# Module_I2C_TOF.net
KiCad netlist of a schematic drawn in EAGLE
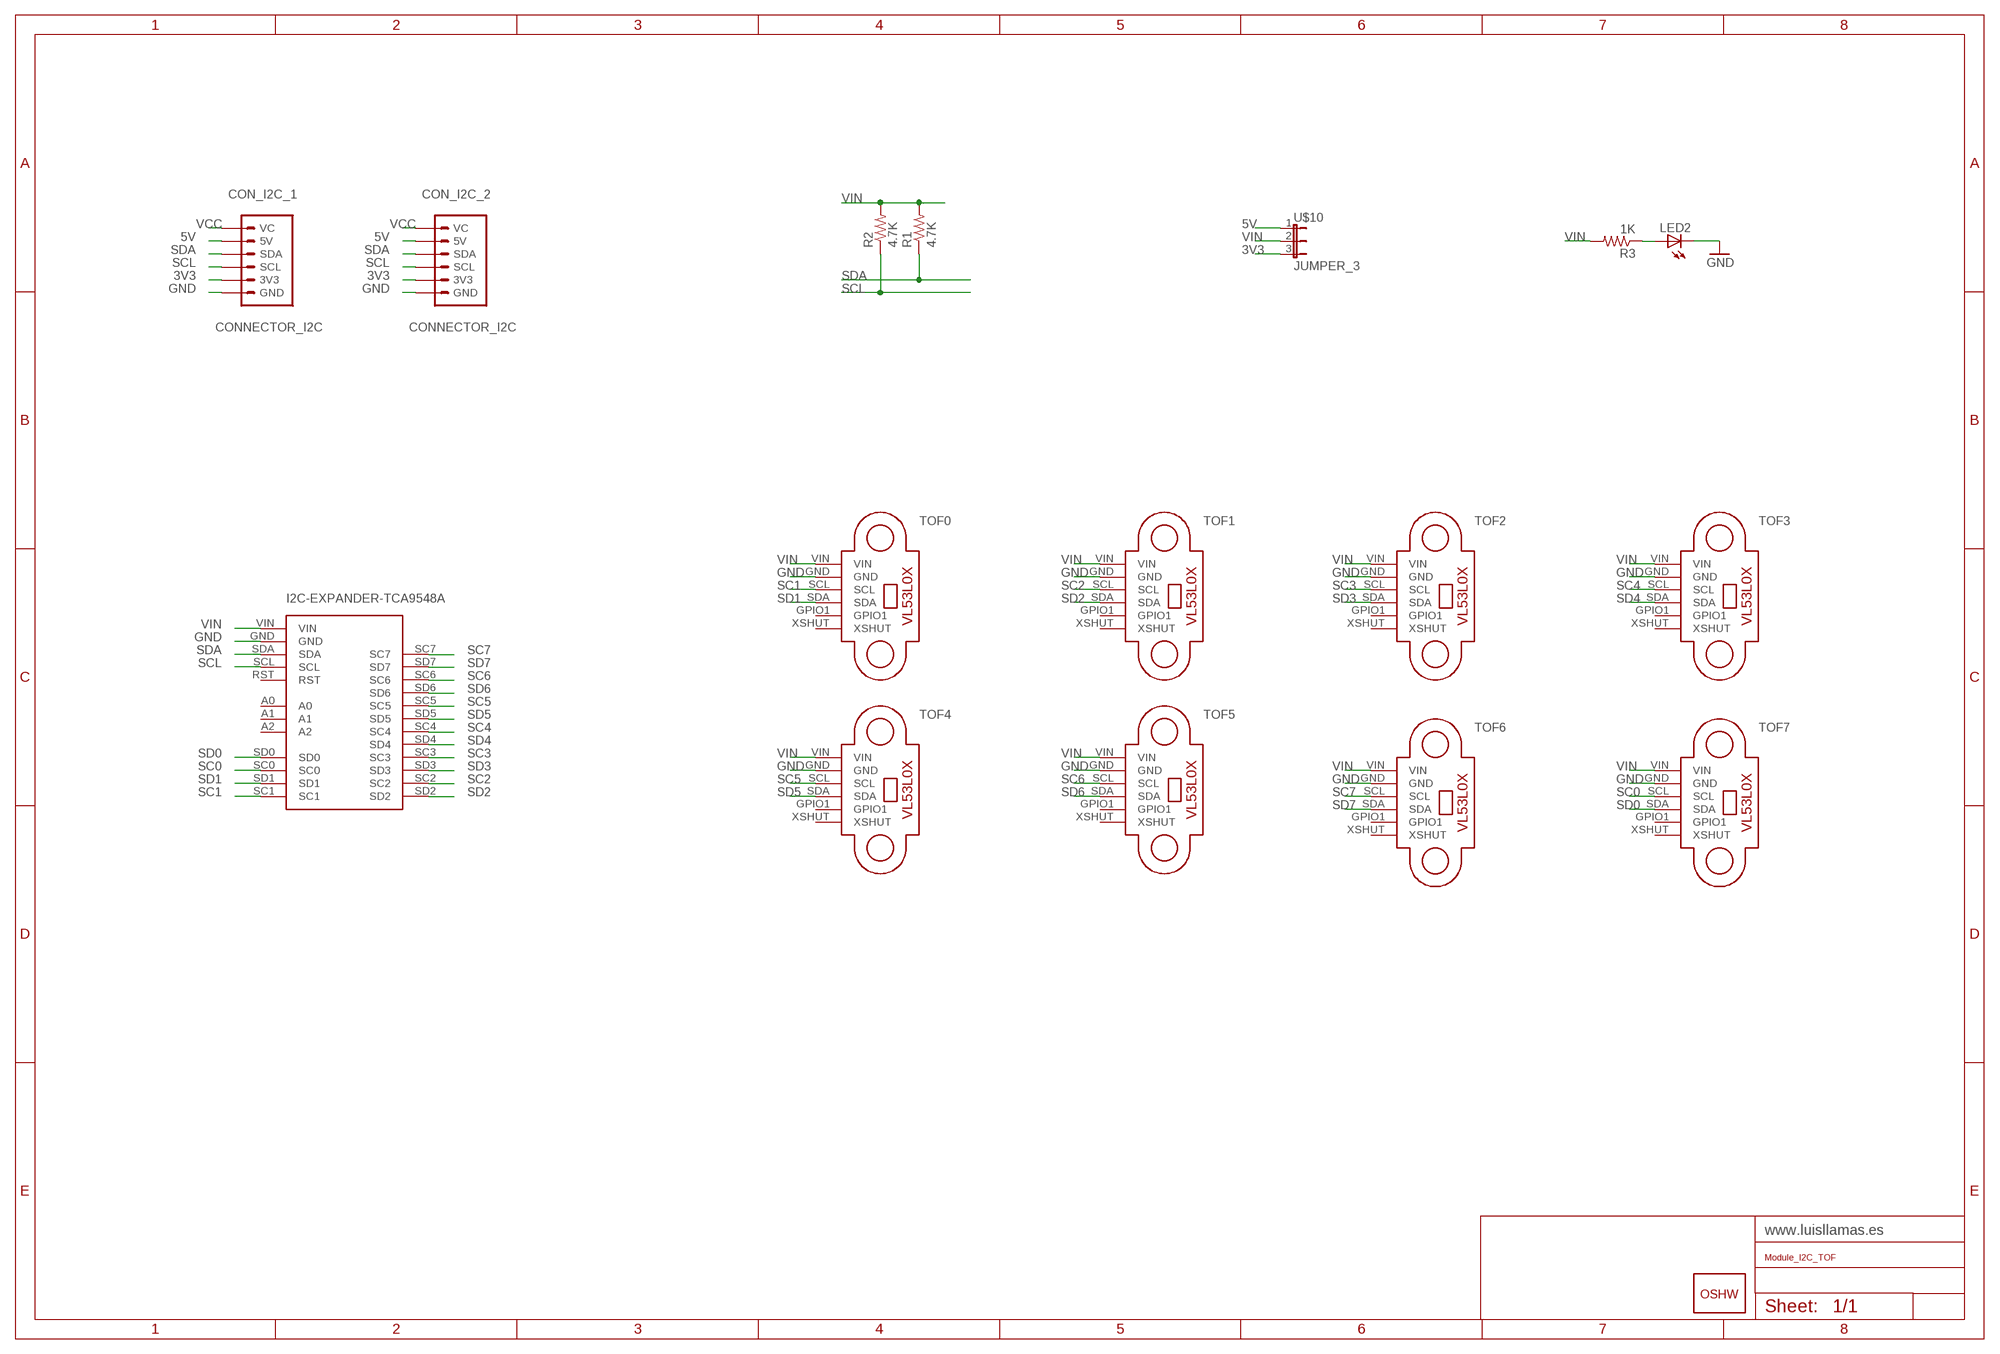
[diagram p0: schematic, sheet 1]

(export (version "E")
  (design (tool "Eeschema 10.0.6"))
  (components
    (comp (ref "CON_I2C_1")
      (value "CONNECTOR_I2C")
      (footprint "eagle-import:CONNECTOR_I2C")
      (libsource (lib "eagle-import") (part "CONNECTOR_I2C"))
    )
    (comp (ref "CON_I2C_2")
      (value "CONNECTOR_I2C")
      (footprint "eagle-import:CONNECTOR_I2C")
      (libsource (lib "eagle-import") (part "CONNECTOR_I2C"))
    )
    (comp (ref "GOLD_ORB_SM1")
      (value "OSHWLOGO_GOLD_ORB_MED")
      (footprint "eagle-import:OSHW1")
      (libsource (lib "eagle-import") (part "OSHWLOGO_GOLD_ORB_MED"))
    )
    (comp (ref "LED2")
      (value "LEDCHIP-LED0805")
      (footprint "eagle-import:CHIP-LED0805")
      (libsource (lib "eagle-import") (part "LEDCHIP-LED0805"))
    )
    (comp (ref "R1")
      (value "4.7K")
      (footprint "eagle-import:R0805")
      (libsource (lib "eagle-import") (part "R-US_R0805"))
    )
    (comp (ref "R2")
      (value "4.7K")
      (footprint "eagle-import:R0805")
      (libsource (lib "eagle-import") (part "R-US_R0805"))
    )
    (comp (ref "R3")
      (value "1K")
      (footprint "eagle-import:R0805")
      (libsource (lib "eagle-import") (part "R-US_R0805"))
    )
    (comp (ref "TOF0")
      (value "RANGING-SENSOR-VL53L0X")
      (footprint "eagle-import:RANGING-SENSOR-VL53L0X")
      (libsource (lib "eagle-import") (part "RANGING-SENSOR-VL53L0X"))
    )
    (comp (ref "TOF1")
      (value "RANGING-SENSOR-VL53L0X")
      (footprint "eagle-import:RANGING-SENSOR-VL53L0X")
      (libsource (lib "eagle-import") (part "RANGING-SENSOR-VL53L0X"))
    )
    (comp (ref "TOF2")
      (value "RANGING-SENSOR-VL53L0X")
      (footprint "eagle-import:RANGING-SENSOR-VL53L0X")
      (libsource (lib "eagle-import") (part "RANGING-SENSOR-VL53L0X"))
    )
    (comp (ref "TOF3")
      (value "RANGING-SENSOR-VL53L0X")
      (footprint "eagle-import:RANGING-SENSOR-VL53L0X")
      (libsource (lib "eagle-import") (part "RANGING-SENSOR-VL53L0X"))
    )
    (comp (ref "TOF4")
      (value "RANGING-SENSOR-VL53L0X")
      (footprint "eagle-import:RANGING-SENSOR-VL53L0X")
      (libsource (lib "eagle-import") (part "RANGING-SENSOR-VL53L0X"))
    )
    (comp (ref "TOF5")
      (value "RANGING-SENSOR-VL53L0X")
      (footprint "eagle-import:RANGING-SENSOR-VL53L0X")
      (libsource (lib "eagle-import") (part "RANGING-SENSOR-VL53L0X"))
    )
    (comp (ref "TOF6")
      (value "RANGING-SENSOR-VL53L0X")
      (footprint "eagle-import:RANGING-SENSOR-VL53L0X")
      (libsource (lib "eagle-import") (part "RANGING-SENSOR-VL53L0X"))
    )
    (comp (ref "TOF7")
      (value "RANGING-SENSOR-VL53L0X")
      (footprint "eagle-import:RANGING-SENSOR-VL53L0X")
      (libsource (lib "eagle-import") (part "RANGING-SENSOR-VL53L0X"))
    )
    (comp (ref "U$9")
      (value "I2C-EXPANDER-TCA9548A")
      (footprint "eagle-import:I2C-EXPANDER-TCA9548A")
      (libsource (lib "eagle-import") (part "I2C-EXPANDER-TCA9548A"))
    )
    (comp (ref "U$10")
      (value "JUMPER_3")
      (footprint "eagle-import:JUMPER_3")
      (libsource (lib "eagle-import") (part "JUMPER_3"))
    )
  )
  (nets
    (net (code "1") (name "/3V3") (class "Default")
      (node (ref "CON_I2C_1") (pin "3V3") (pinfunction "3V3_3V3") (pintype "passive"))
      (node (ref "CON_I2C_2") (pin "3V3") (pinfunction "3V3_3V3") (pintype "passive"))
      (node (ref "U$10") (pin "3") (pinfunction "3_3") (pintype "passive"))
    )
    (net (code "2") (name "/5V") (class "Default")
      (node (ref "CON_I2C_1") (pin "5V") (pinfunction "5V_5V") (pintype "passive"))
      (node (ref "CON_I2C_2") (pin "5V") (pinfunction "5V_5V") (pintype "passive"))
      (node (ref "U$10") (pin "1") (pinfunction "1_1") (pintype "passive"))
    )
    (net (code "3") (name "/SC0") (class "Default")
      (node (ref "TOF7") (pin "SCL") (pinfunction "SCL_SCL") (pintype "bidirectional"))
      (node (ref "U$9") (pin "SC0") (pinfunction "SC0_SC0") (pintype "input"))
    )
    (net (code "4") (name "/SC1") (class "Default")
      (node (ref "TOF0") (pin "SCL") (pinfunction "SCL_SCL") (pintype "bidirectional"))
      (node (ref "U$9") (pin "SC1") (pinfunction "SC1_SC1") (pintype "input"))
    )
    (net (code "5") (name "/SC2") (class "Default")
      (node (ref "TOF1") (pin "SCL") (pinfunction "SCL_SCL") (pintype "bidirectional"))
      (node (ref "U$9") (pin "SC2") (pinfunction "SC2_SC2") (pintype "bidirectional"))
    )
    (net (code "6") (name "/SC3") (class "Default")
      (node (ref "TOF2") (pin "SCL") (pinfunction "SCL_SCL") (pintype "bidirectional"))
      (node (ref "U$9") (pin "SC3") (pinfunction "SC3_SC3") (pintype "bidirectional"))
    )
    (net (code "7") (name "/SC4") (class "Default")
      (node (ref "TOF3") (pin "SCL") (pinfunction "SCL_SCL") (pintype "bidirectional"))
      (node (ref "U$9") (pin "SC4") (pinfunction "SC4_SC4") (pintype "input"))
    )
    (net (code "8") (name "/SC5") (class "Default")
      (node (ref "TOF4") (pin "SCL") (pinfunction "SCL_SCL") (pintype "bidirectional"))
      (node (ref "U$9") (pin "SC5") (pinfunction "SC5_SC5") (pintype "input"))
    )
    (net (code "9") (name "/SC6") (class "Default")
      (node (ref "TOF5") (pin "SCL") (pinfunction "SCL_SCL") (pintype "bidirectional"))
      (node (ref "U$9") (pin "SC6") (pinfunction "SC6_SC6") (pintype "input"))
    )
    (net (code "10") (name "/SC7") (class "Default")
      (node (ref "TOF6") (pin "SCL") (pinfunction "SCL_SCL") (pintype "bidirectional"))
      (node (ref "U$9") (pin "SC7") (pinfunction "SC7_SC7") (pintype "input"))
    )
    (net (code "11") (name "/SCL") (class "Default")
      (node (ref "CON_I2C_1") (pin "SCL") (pinfunction "SCL_SCL") (pintype "passive"))
      (node (ref "CON_I2C_2") (pin "SCL") (pinfunction "SCL_SCL") (pintype "passive"))
      (node (ref "R2") (pin "1") (pinfunction "1_1") (pintype "passive"))
      (node (ref "U$9") (pin "SCL") (pinfunction "SCL_SCL") (pintype "bidirectional"))
    )
    (net (code "12") (name "/SD0") (class "Default")
      (node (ref "TOF7") (pin "SDA") (pinfunction "SDA_SDA") (pintype "bidirectional"))
      (node (ref "U$9") (pin "SD0") (pinfunction "SD0_SD0") (pintype "input"))
    )
    (net (code "13") (name "/SD1") (class "Default")
      (node (ref "TOF0") (pin "SDA") (pinfunction "SDA_SDA") (pintype "bidirectional"))
      (node (ref "U$9") (pin "SD1") (pinfunction "SD1_SD1") (pintype "input"))
    )
    (net (code "14") (name "/SD2") (class "Default")
      (node (ref "TOF1") (pin "SDA") (pinfunction "SDA_SDA") (pintype "bidirectional"))
      (node (ref "U$9") (pin "SD2") (pinfunction "SD2_SD2") (pintype "bidirectional"))
    )
    (net (code "15") (name "/SD3") (class "Default")
      (node (ref "TOF2") (pin "SDA") (pinfunction "SDA_SDA") (pintype "bidirectional"))
      (node (ref "U$9") (pin "SD3") (pinfunction "SD3_SD3") (pintype "bidirectional"))
    )
    (net (code "16") (name "/SD4") (class "Default")
      (node (ref "TOF3") (pin "SDA") (pinfunction "SDA_SDA") (pintype "bidirectional"))
      (node (ref "U$9") (pin "SD4") (pinfunction "SD4_SD4") (pintype "input"))
    )
    (net (code "17") (name "/SD5") (class "Default")
      (node (ref "TOF4") (pin "SDA") (pinfunction "SDA_SDA") (pintype "bidirectional"))
      (node (ref "U$9") (pin "SD5") (pinfunction "SD5_SD5") (pintype "input"))
    )
    (net (code "18") (name "/SD6") (class "Default")
      (node (ref "TOF5") (pin "SDA") (pinfunction "SDA_SDA") (pintype "bidirectional"))
      (node (ref "U$9") (pin "SD6") (pinfunction "SD6_SD6") (pintype "input"))
    )
    (net (code "19") (name "/SD7") (class "Default")
      (node (ref "TOF6") (pin "SDA") (pinfunction "SDA_SDA") (pintype "bidirectional"))
      (node (ref "U$9") (pin "SD7") (pinfunction "SD7_SD7") (pintype "input"))
    )
    (net (code "20") (name "/SDA") (class "Default")
      (node (ref "CON_I2C_1") (pin "SDA") (pinfunction "SDA_SDA") (pintype "passive"))
      (node (ref "CON_I2C_2") (pin "SDA") (pinfunction "SDA_SDA") (pintype "passive"))
      (node (ref "R1") (pin "1") (pinfunction "1_1") (pintype "passive"))
      (node (ref "U$9") (pin "SDA") (pinfunction "SDA_SDA") (pintype "bidirectional"))
    )
    (net (code "21") (name "/VCC") (class "Default")
      (node (ref "CON_I2C_1") (pin "VC") (pinfunction "VC_VC") (pintype "passive"))
      (node (ref "CON_I2C_2") (pin "VC") (pinfunction "VC_VC") (pintype "passive"))
    )
    (net (code "22") (name "/VIN") (class "Default")
      (node (ref "R1") (pin "2") (pinfunction "2_2") (pintype "passive"))
      (node (ref "R2") (pin "2") (pinfunction "2_2") (pintype "passive"))
      (node (ref "R3") (pin "2") (pinfunction "2_2") (pintype "passive"))
      (node (ref "TOF0") (pin "VIN") (pinfunction "VIN_VIN") (pintype "power_in"))
      (node (ref "TOF1") (pin "VIN") (pinfunction "VIN_VIN") (pintype "power_in"))
      (node (ref "TOF2") (pin "VIN") (pinfunction "VIN_VIN") (pintype "power_in"))
      (node (ref "TOF3") (pin "VIN") (pinfunction "VIN_VIN") (pintype "power_in"))
      (node (ref "TOF4") (pin "VIN") (pinfunction "VIN_VIN") (pintype "power_in"))
      (node (ref "TOF5") (pin "VIN") (pinfunction "VIN_VIN") (pintype "power_in"))
      (node (ref "TOF6") (pin "VIN") (pinfunction "VIN_VIN") (pintype "power_in"))
      (node (ref "TOF7") (pin "VIN") (pinfunction "VIN_VIN") (pintype "power_in"))
      (node (ref "U$10") (pin "2") (pinfunction "2_2") (pintype "passive"))
      (node (ref "U$9") (pin "VIN") (pinfunction "VIN_VIN") (pintype "power_in"))
    )
    (net (code "23") (name "GND") (class "Default")
      (node (ref "CON_I2C_1") (pin "GND") (pinfunction "GND_GND") (pintype "passive"))
      (node (ref "CON_I2C_2") (pin "GND") (pinfunction "GND_GND") (pintype "passive"))
      (node (ref "LED2") (pin "C") (pinfunction "C_C") (pintype "passive"))
      (node (ref "TOF0") (pin "GND") (pinfunction "GND_GND") (pintype "power_in"))
      (node (ref "TOF1") (pin "GND") (pinfunction "GND_GND") (pintype "power_in"))
      (node (ref "TOF2") (pin "GND") (pinfunction "GND_GND") (pintype "power_in"))
      (node (ref "TOF3") (pin "GND") (pinfunction "GND_GND") (pintype "power_in"))
      (node (ref "TOF4") (pin "GND") (pinfunction "GND_GND") (pintype "power_in"))
      (node (ref "TOF5") (pin "GND") (pinfunction "GND_GND") (pintype "power_in"))
      (node (ref "TOF6") (pin "GND") (pinfunction "GND_GND") (pintype "power_in"))
      (node (ref "TOF7") (pin "GND") (pinfunction "GND_GND") (pintype "power_in"))
      (node (ref "U$9") (pin "GND") (pinfunction "GND_GND") (pintype "power_in"))
    )
    (net (code "24") (name "Net-(LED2-PadA)") (class "Default")
      (node (ref "LED2") (pin "A") (pinfunction "A_A") (pintype "passive"))
      (node (ref "R3") (pin "1") (pinfunction "1_1") (pintype "passive"))
    )
    (net (code "25") (name "unconnected-(TOF0-PadGPIO1)") (class "Default")
      (node (ref "TOF0") (pin "GPIO1") (pinfunction "GPIO1_GPIO1") (pintype "bidirectional"))
    )
    (net (code "26") (name "unconnected-(TOF0-PadXSHUT)") (class "Default")
      (node (ref "TOF0") (pin "XSHUT") (pinfunction "XSHUT_XSHUT") (pintype "bidirectional"))
    )
    (net (code "27") (name "unconnected-(TOF1-PadGPIO1)") (class "Default")
      (node (ref "TOF1") (pin "GPIO1") (pinfunction "GPIO1_GPIO1") (pintype "bidirectional"))
    )
    (net (code "28") (name "unconnected-(TOF1-PadXSHUT)") (class "Default")
      (node (ref "TOF1") (pin "XSHUT") (pinfunction "XSHUT_XSHUT") (pintype "bidirectional"))
    )
    (net (code "29") (name "unconnected-(TOF2-PadGPIO1)") (class "Default")
      (node (ref "TOF2") (pin "GPIO1") (pinfunction "GPIO1_GPIO1") (pintype "bidirectional"))
    )
    (net (code "30") (name "unconnected-(TOF2-PadXSHUT)") (class "Default")
      (node (ref "TOF2") (pin "XSHUT") (pinfunction "XSHUT_XSHUT") (pintype "bidirectional"))
    )
    (net (code "31") (name "unconnected-(TOF3-PadGPIO1)") (class "Default")
      (node (ref "TOF3") (pin "GPIO1") (pinfunction "GPIO1_GPIO1") (pintype "bidirectional"))
    )
    (net (code "32") (name "unconnected-(TOF3-PadXSHUT)") (class "Default")
      (node (ref "TOF3") (pin "XSHUT") (pinfunction "XSHUT_XSHUT") (pintype "bidirectional"))
    )
    (net (code "33") (name "unconnected-(TOF4-PadGPIO1)") (class "Default")
      (node (ref "TOF4") (pin "GPIO1") (pinfunction "GPIO1_GPIO1") (pintype "bidirectional"))
    )
    (net (code "34") (name "unconnected-(TOF4-PadXSHUT)") (class "Default")
      (node (ref "TOF4") (pin "XSHUT") (pinfunction "XSHUT_XSHUT") (pintype "bidirectional"))
    )
    (net (code "35") (name "unconnected-(TOF5-PadGPIO1)") (class "Default")
      (node (ref "TOF5") (pin "GPIO1") (pinfunction "GPIO1_GPIO1") (pintype "bidirectional"))
    )
    (net (code "36") (name "unconnected-(TOF5-PadXSHUT)") (class "Default")
      (node (ref "TOF5") (pin "XSHUT") (pinfunction "XSHUT_XSHUT") (pintype "bidirectional"))
    )
    (net (code "37") (name "unconnected-(TOF6-PadGPIO1)") (class "Default")
      (node (ref "TOF6") (pin "GPIO1") (pinfunction "GPIO1_GPIO1") (pintype "bidirectional"))
    )
    (net (code "38") (name "unconnected-(TOF6-PadXSHUT)") (class "Default")
      (node (ref "TOF6") (pin "XSHUT") (pinfunction "XSHUT_XSHUT") (pintype "bidirectional"))
    )
    (net (code "39") (name "unconnected-(TOF7-PadGPIO1)") (class "Default")
      (node (ref "TOF7") (pin "GPIO1") (pinfunction "GPIO1_GPIO1") (pintype "bidirectional"))
    )
    (net (code "40") (name "unconnected-(TOF7-PadXSHUT)") (class "Default")
      (node (ref "TOF7") (pin "XSHUT") (pinfunction "XSHUT_XSHUT") (pintype "bidirectional"))
    )
    (net (code "41") (name "unconnected-(U$9-PadA0)") (class "Default")
      (node (ref "U$9") (pin "A0") (pinfunction "A0_A0") (pintype "input"))
    )
    (net (code "42") (name "unconnected-(U$9-PadA1)") (class "Default")
      (node (ref "U$9") (pin "A1") (pinfunction "A1_A1") (pintype "input"))
    )
    (net (code "43") (name "unconnected-(U$9-PadA2)") (class "Default")
      (node (ref "U$9") (pin "A2") (pinfunction "A2_A2") (pintype "input"))
    )
    (net (code "44") (name "unconnected-(U$9-PadRST)") (class "Default")
      (node (ref "U$9") (pin "RST") (pinfunction "RST_RST") (pintype "bidirectional"))
    )
  )
)
